# Power_Management.net
KiCad netlist of a schematic drawn in Altium Designer
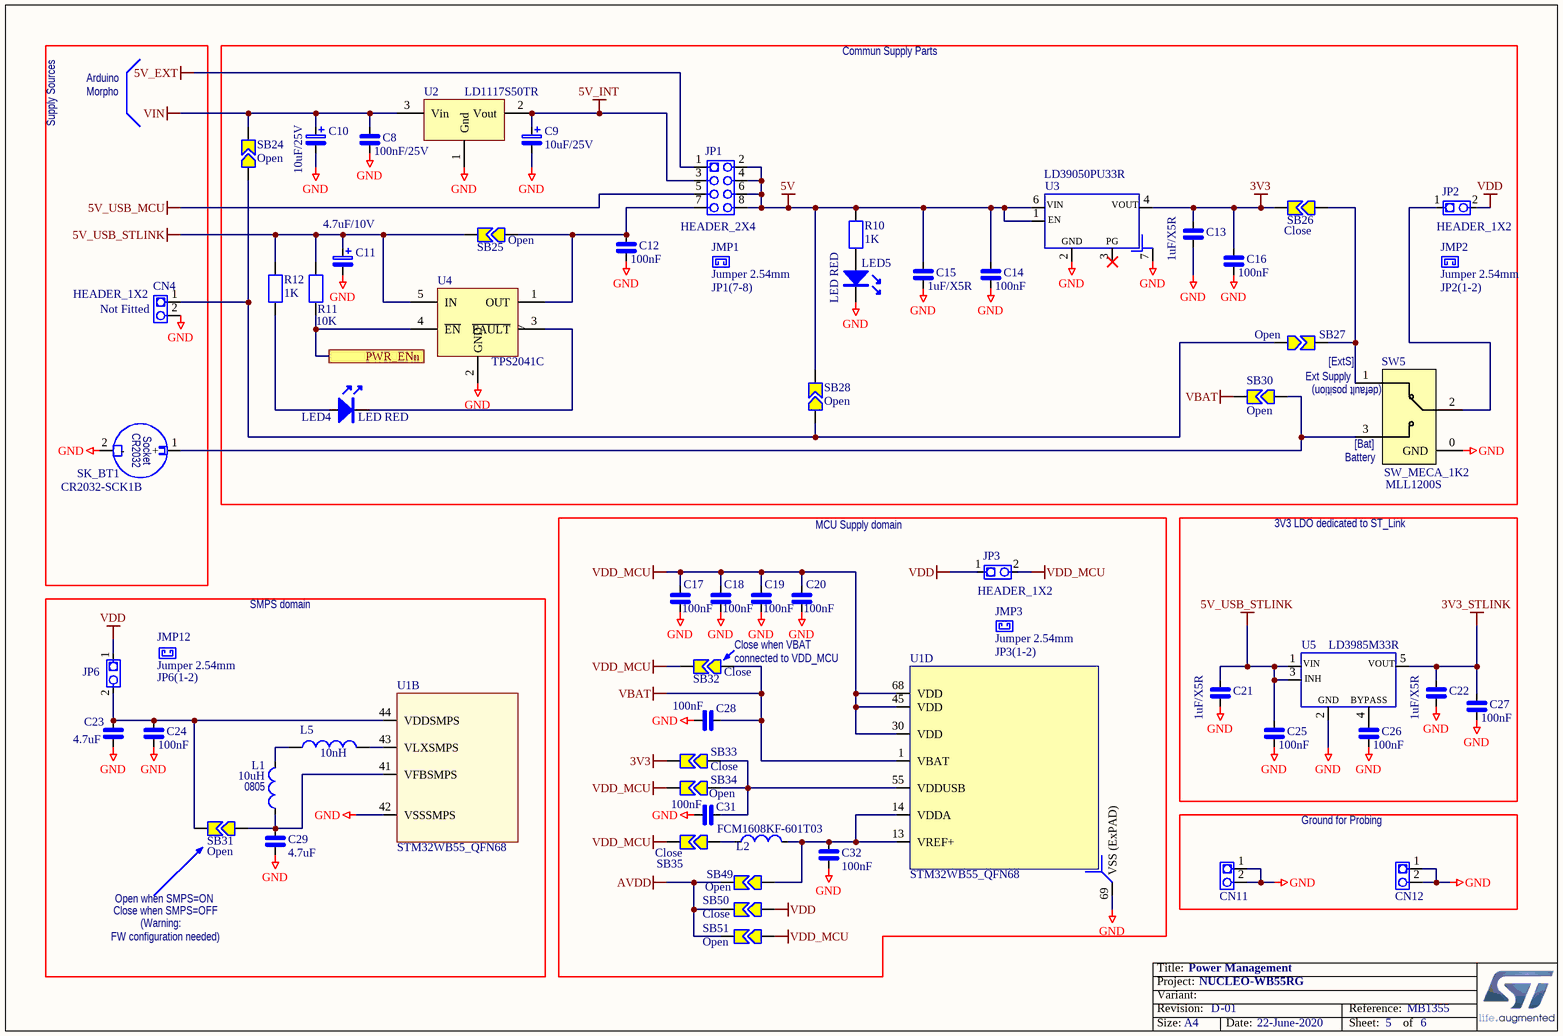
[diagram p0: Power_Management.SchDoc]

(export (version "E")
  (design (tool "Eeschema 10.0.6"))
  (components
    (comp (ref "C8")
      (value "100nF/25V")
      (footprint "0402_CAP_NPOL")
      (description "Capacitor_not polarized")
      (libsource (lib "ST_Lib3D") (part "CAP_NPOL"))
    )
    (comp (ref "C9")
      (value "10uF/25V")
      (footprint "1210_CAP_POL")
      (description "Condensateur_polarise")
      (libsource (lib "Passive") (part "CAP_POL"))
    )
    (comp (ref "C10")
      (value "10uF/25V")
      (footprint "1210_CAP_POL")
      (description "Condensateur_polarise")
      (libsource (lib "Passive") (part "CAP_POL"))
    )
    (comp (ref "C11")
      (value "4.7uF/10V")
      (footprint "1210_CAP_POL")
      (description "Condensateur_polarise")
      (libsource (lib "Passive") (part "CAP_POL"))
    )
    (comp (ref "C12")
      (value "100nF")
      (footprint "0402_CAP_NPOL")
      (description "Capacitor_not polarized")
      (libsource (lib "ST_Lib3D") (part "CAP_NPOL"))
    )
    (comp (ref "C13")
      (value "1uF/X5R")
      (footprint "0603_CAP_NPOL")
      (description "Capacitor_not polarized")
      (libsource (lib "ST_Lib3D") (part "CAP_NPOL"))
    )
    (comp (ref "C14")
      (value "100nF")
      (footprint "0402_CAP_NPOL")
      (description "Capacitor_not polarized")
      (libsource (lib "ST_Lib3D") (part "CAP_NPOL"))
    )
    (comp (ref "C15")
      (value "1uF/X5R")
      (footprint "0603_CAP_NPOL")
      (description "Capacitor_not polarized")
      (libsource (lib "ST_Lib3D") (part "CAP_NPOL"))
    )
    (comp (ref "C16")
      (value "100nF")
      (footprint "0402_CAP_NPOL")
      (description "Capacitor_not polarized")
      (libsource (lib "ST_Lib3D") (part "CAP_NPOL"))
    )
    (comp (ref "C17")
      (value "100nF")
      (footprint "0402_CAP_NPOL")
      (description "Capacitor_not polarized")
      (libsource (lib "ST_Lib3D") (part "CAP_NPOL"))
    )
    (comp (ref "C18")
      (value "100nF")
      (footprint "0402_CAP_NPOL")
      (description "Capacitor_not polarized")
      (libsource (lib "ST_Lib3D") (part "CAP_NPOL"))
    )
    (comp (ref "C19")
      (value "100nF")
      (footprint "0402_CAP_NPOL")
      (description "Capacitor_not polarized")
      (libsource (lib "ST_Lib3D") (part "CAP_NPOL"))
    )
    (comp (ref "C20")
      (value "100nF")
      (footprint "0402_CAP_NPOL")
      (description "Capacitor_not polarized")
      (libsource (lib "ST_Lib3D") (part "CAP_NPOL"))
    )
    (comp (ref "C21")
      (value "1uF/X5R")
      (footprint "0603_CAP_NPOL")
      (description "Capacitor_not polarized")
      (libsource (lib "ST_Lib3D") (part "CAP_NPOL"))
    )
    (comp (ref "C22")
      (value "1uF/X5R")
      (footprint "0603_CAP_NPOL")
      (description "Capacitor_not polarized")
      (libsource (lib "ST_Lib3D") (part "CAP_NPOL"))
    )
    (comp (ref "C23")
      (value "4.7uF")
      (footprint "0402_CAP_NPOL")
      (description "Capacitor_not polarized")
      (libsource (lib "ST_Lib3D") (part "CAP_NPOL"))
    )
    (comp (ref "C24")
      (value "100nF")
      (footprint "0402_CAP_NPOL")
      (description "Capacitor_not polarized")
      (libsource (lib "ST_Lib3D") (part "CAP_NPOL"))
    )
    (comp (ref "C25")
      (value "100nF")
      (footprint "0402_CAP_NPOL")
      (description "Capacitor_not polarized")
      (libsource (lib "ST_Lib3D") (part "CAP_NPOL"))
    )
    (comp (ref "C26")
      (value "100nF")
      (footprint "0402_CAP_NPOL")
      (description "Capacitor_not polarized")
      (libsource (lib "ST_Lib3D") (part "CAP_NPOL"))
    )
    (comp (ref "C27")
      (value "100nF")
      (footprint "0402_CAP_NPOL")
      (description "Capacitor_not polarized")
      (libsource (lib "ST_Lib3D") (part "CAP_NPOL"))
    )
    (comp (ref "C28")
      (value "100nF")
      (footprint "0402_CAP_NPOL")
      (description "Capacitor_not polarized")
      (libsource (lib "ST_Lib3D") (part "CAP_NPOL"))
    )
    (comp (ref "C29")
      (value "4.7uF")
      (footprint "0402_CAP_NPOL")
      (description "Capacitor_not polarized")
      (libsource (lib "ST_Lib3D") (part "CAP_NPOL"))
    )
    (comp (ref "C31")
      (value "100nF")
      (footprint "0402_CAP_NPOL")
      (description "Capacitor_not polarized")
      (libsource (lib "ST_Lib3D") (part "CAP_NPOL"))
    )
    (comp (ref "C32")
      (value "100nF")
      (footprint "0402_CAP_NPOL")
      (description "Capacitor_not polarized")
      (libsource (lib "ST_Lib3D") (part "CAP_NPOL"))
    )
    (comp (ref "CN4")
      (value "HEADER_1X2")
      (footprint "Header NF 1x2x2.54 TH")
      (fields (field (name "FITTED") "Not Fitted"))
      (libsource (lib "Connector") (part "HEADER_1X2"))
    )
    (comp (ref "CN11")
      (value "HEADER_1X2")
      (footprint "Header M 1x2x2.54 TH V")
      (libsource (lib "Connector") (part "HEADER_1X2"))
    )
    (comp (ref "CN12")
      (value "HEADER_1X2")
      (footprint "Header M 1x2x2.54 TH V")
      (libsource (lib "Connector") (part "HEADER_1X2"))
    )
    (comp (ref "JMP1")
      (value "Jumper 2.54mm")
      (footprint "Jumper 2.54mm BLACK")
      (fields (field (name "DEFAULT") "JP1(7-8)"))
      (libsource (lib "Connector") (part "Jumper 2.54mm"))
    )
    (comp (ref "JMP2")
      (value "Jumper 2.54mm")
      (footprint "Jumper 2.54mm BLACK")
      (fields (field (name "DEFAULT") "JP2(1-2)"))
      (libsource (lib "Connector") (part "Jumper 2.54mm"))
    )
    (comp (ref "JMP3")
      (value "Jumper 2.54mm")
      (footprint "Jumper 2.54mm BLACK")
      (fields (field (name "DEFAULT") "JP3(1-2)"))
      (libsource (lib "Connector") (part "Jumper 2.54mm"))
    )
    (comp (ref "JMP12")
      (value "Jumper 2.54mm")
      (footprint "Jumper 2.54mm BLACK")
      (fields (field (name "DEFAULT") "JP6(1-2)"))
      (libsource (lib "Connector") (part "Jumper 2.54mm"))
    )
    (comp (ref "JP1")
      (value "HEADER_2X4")
      (footprint "Header M 2x4x2.54 TH V")
      (libsource (lib "Connector") (part "HEADER_2X4"))
    )
    (comp (ref "JP2")
      (value "HEADER_1X2")
      (footprint "Header M 1x2x2.54 TH V")
      (libsource (lib "Connector") (part "HEADER_1X2_L"))
    )
    (comp (ref "JP3")
      (value "HEADER_1X2")
      (footprint "Header M 1x2x2.54 TH V")
      (libsource (lib "Connector") (part "HEADER_1X2_L"))
    )
    (comp (ref "JP6")
      (value "HEADER_1X2")
      (footprint "Header M 1x2x2.54 TH V")
      (libsource (lib "Connector") (part "HEADER_1X2_L"))
    )
    (comp (ref "L1")
      (value "10uH")
      (footprint "0805_COIL")
      (description "Coil Wurtz 10uH ref: 74479777310A")
      (libsource (lib "Passive") (part "IND_74479777310A"))
    )
    (comp (ref "L2")
      (value "FCM1608KF-601T03")
      (footprint "0603_COIL")
      (libsource (lib "Passive") (part "IND_FCM1608KF-601T03"))
    )
    (comp (ref "L5")
      (value "10nH")
      (footprint "IND_0402_MURATA_LQW15AN_H0P5")
      (description "inductor, 10nH +-2%, 100mA max,1.3 ohm DC max, Q min = 13,0402")
      (fields
        (field (name "INTERNAL_PART_NUMBER") "MCD-02063")
        (field (name "MANUFACTURER_PART_NUMBER") "LQP15MN10NG02")
        (field (name "PROVIDED_BY") "SUBCO")
      )
      (libsource (lib "MCD_PARTS_database") (part "Inductor"))
    )
    (comp (ref "LED4")
      (value "LED RED")
      (footprint "0603_LED_RED")
      (description "Light-Emitting Diode")
      (libsource (lib "Active") (part "LED"))
    )
    (comp (ref "LED5")
      (value "LED RED")
      (footprint "0603_LED_RED")
      (description "Light-Emitting Diode")
      (libsource (lib "Active") (part "LED"))
    )
    (comp (ref "R10")
      (value "1K")
      (footprint "0402_RES")
      (description "Resistor")
      (libsource (lib "Lib3D_Altium10_Schlib") (part "RES"))
    )
    (comp (ref "R11")
      (value "10K")
      (footprint "0402_RES")
      (description "Resistor")
      (libsource (lib "Lib3D_Altium10_Schlib") (part "RES"))
    )
    (comp (ref "R12")
      (value "1K")
      (footprint "0402_RES")
      (description "Resistor")
      (libsource (lib "Lib3D_Altium10_Schlib") (part "RES"))
    )
    (comp (ref "SB24")
      (value "Open")
      (footprint "SB-tiny")
      (description "Solder Jumper")
      (fields (field (name "PUBLISHER") "Altium Limited"))
      (libsource (lib "Passive") (part "Strap2"))
    )
    (comp (ref "SB25")
      (value "Open")
      (footprint "SB-tiny")
      (description "Solder Jumper")
      (fields (field (name "PUBLISHER") "Altium Limited"))
      (libsource (lib "Passive") (part "Strap2"))
    )
    (comp (ref "SB26")
      (value "Close")
      (footprint "SB-tiny")
      (description "Solder Jumper")
      (fields (field (name "PUBLISHER") "Altium Limited"))
      (libsource (lib "Passive") (part "Strap2"))
    )
    (comp (ref "SB27")
      (value "Open")
      (footprint "SB-tiny")
      (description "Solder Jumper")
      (fields (field (name "PUBLISHER") "Altium Limited"))
      (libsource (lib "Passive") (part "Strap2"))
    )
    (comp (ref "SB28")
      (value "Open")
      (footprint "SB-tiny")
      (description "Solder Jumper")
      (fields (field (name "PUBLISHER") "Altium Limited"))
      (libsource (lib "Passive") (part "Strap2"))
    )
    (comp (ref "SB30")
      (value "Open")
      (footprint "SB-tiny")
      (description "Solder Jumper")
      (fields (field (name "PUBLISHER") "Altium Limited"))
      (libsource (lib "Passive") (part "Strap2"))
    )
    (comp (ref "SB31")
      (value "Open")
      (footprint "SB-tiny")
      (description "Solder Jumper")
      (fields (field (name "PUBLISHER") "Altium Limited"))
      (libsource (lib "Passive") (part "Strap2"))
    )
    (comp (ref "SB32")
      (value "Close")
      (footprint "SB-tiny")
      (description "Solder Jumper")
      (fields (field (name "PUBLISHER") "Altium Limited"))
      (libsource (lib "Passive") (part "Strap2"))
    )
    (comp (ref "SB33")
      (value "Close")
      (footprint "SB-tiny")
      (description "Solder Jumper")
      (fields (field (name "PUBLISHER") "Altium Limited"))
      (libsource (lib "Passive") (part "Strap2"))
    )
    (comp (ref "SB34")
      (value "Open")
      (footprint "SB-tiny")
      (description "Solder Jumper")
      (fields (field (name "PUBLISHER") "Altium Limited"))
      (libsource (lib "Passive") (part "Strap2"))
    )
    (comp (ref "SB35")
      (value "Close")
      (footprint "SB-tiny")
      (description "Solder Jumper")
      (fields (field (name "PUBLISHER") "Altium Limited"))
      (libsource (lib "Passive") (part "Strap2"))
    )
    (comp (ref "SB49")
      (value "Open")
      (footprint "SB-tiny")
      (description "Solder Jumper")
      (fields (field (name "PUBLISHER") "Altium Limited"))
      (libsource (lib "Passive") (part "Strap2"))
    )
    (comp (ref "SB50")
      (value "Close")
      (footprint "SB-tiny")
      (description "Solder Jumper")
      (fields (field (name "PUBLISHER") "Altium Limited"))
      (libsource (lib "Passive") (part "Strap2"))
    )
    (comp (ref "SB51")
      (value "Open")
      (footprint "SB-tiny")
      (description "Solder Jumper")
      (fields (field (name "PUBLISHER") "Altium Limited"))
      (libsource (lib "Passive") (part "Strap2"))
    )
    (comp (ref "SK_BT1")
      (value "CR2032-SCK1B")
      (footprint "CR2032-SCK1")
      (libsource (lib "Battery_Acc_Generator") (part "CR2032-SCK1B"))
    )
    (comp (ref "SW5")
      (value "SW_MECA_1K2")
      (footprint "SWI_SPDT-RA_TE-CONNECTIVITY_MLL1200S_1P2T")
      (description "SPDT RA SMT SLIDE SWITCH")
      (fields
        (field (name "INTERNAL_PART_NUMBER") "MCD-02081")
        (field (name "ALTIUM_VALUE") "MLL1200S")
        (field (name "MANUFACTURER_PART_NUMBER") "MLL1200S")
        (field (name "PROVIDED_BY") "SUBCO")
      )
      (libsource (lib "MCD_PARTS_database") (part "SW_MECA_1K2"))
    )
    (comp (ref "U1")
      (value "STM32WB55_QFN68")
      (footprint "VFQFPN68_8x8x0.1_p0.4")
      (libsource (lib "Active") (part "STM32WBxx_QFN68"))
    )
    (comp (ref "U2")
      (value "LD1117S50TR")
      (footprint "SOT223_SC73_A")
      (description "IC REG LDO 5V 0.8A SOT223")
      (libsource (lib "Active") (part "LD1117S50TR"))
    )
    (comp (ref "U3")
      (value "LD39050PU33R")
      (footprint "DFN6 3x3mm")
      (description "3.3V voltage regulator 500mA")
      (libsource (lib "Active") (part "LD39050PU33R"))
    )
    (comp (ref "U4")
      (value "TPS2041C")
      (footprint "MOS_SOT23-5L")
      (description "5V Power Switch, 0.85A, RDSon 130mOhm max, with active low enable pin")
      (fields
        (field (name "INTERNAL_PART_NUMBER") "MCD-01785")
        (field (name "MANUFACTURER_PART_NUMBER") "TPS2041CDBVT")
        (field (name "PROVIDED_BY") "SUBCO")
      )
      (libsource (lib "MCD_PARTS_database") (part "TPS2041C"))
    )
    (comp (ref "U5")
      (value "LD3985M33R")
      (footprint "SOT23-5")
      (description "3.3V low drop voltage regulator")
      (fields (field (name "MANUFACTURER") "STMicroelectronics"))
      (libsource (lib "Active") (part "LD3985M33R"))
    )
  )
  (nets
    (net (code "1") (name "/PWR_ENn") (class "Default")
      (node (ref "R11") (pin "2") (pinfunction "2_2") (pintype "passive"))
      (node (ref "U4") (pin "4") (pinfunction "~{EN}_4") (pintype "passive"))
    )
    (net (code "2") (name "3V3") (class "Default")
      (node (ref "C13") (pin "1") (pinfunction "1_1") (pintype "passive"))
      (node (ref "C16") (pin "1") (pinfunction "1_1") (pintype "passive"))
      (node (ref "SB26") (pin "2") (pinfunction "2_2") (pintype "passive"))
      (node (ref "SB33") (pin "2") (pinfunction "2_2") (pintype "passive"))
      (node (ref "U3") (pin "4") (pinfunction "VOUT_4") (pintype "passive"))
    )
    (net (code "3") (name "3V3_STLINK") (class "Default")
      (node (ref "C22") (pin "1") (pinfunction "1_1") (pintype "passive"))
      (node (ref "C27") (pin "1") (pinfunction "1_1") (pintype "passive"))
      (node (ref "U5") (pin "5") (pinfunction "VOUT_5") (pintype "passive"))
    )
    (net (code "4") (name "5V") (class "Default")
      (node (ref "C14") (pin "1") (pinfunction "1_1") (pintype "passive"))
      (node (ref "C15") (pin "1") (pinfunction "1_1") (pintype "passive"))
      (node (ref "JP1") (pin "2") (pintype "passive"))
      (node (ref "JP1") (pin "4") (pintype "passive"))
      (node (ref "JP1") (pin "6") (pintype "passive"))
      (node (ref "JP1") (pin "8") (pintype "passive"))
      (node (ref "R10") (pin "1") (pinfunction "1_1") (pintype "passive"))
      (node (ref "SB28") (pin "2") (pinfunction "2_2") (pintype "passive"))
      (node (ref "U3") (pin "1") (pinfunction "EN_1") (pintype "passive"))
      (node (ref "U3") (pin "6") (pinfunction "VIN_6") (pintype "passive"))
    )
    (net (code "5") (name "5V_EXT") (class "Default") (node (ref "JP1") (pin "1") (pintype "passive")))
    (net (code "6") (name "5V_INT") (class "Default")
      (node (ref "C9") (pin "1") (pintype "passive"))
      (node (ref "JP1") (pin "3") (pintype "passive"))
      (node (ref "U2") (pin "2") (pinfunction "Vout_2") (pintype "passive"))
    )
    (net (code "7") (name "5V_USB_MCU") (class "Default") (node (ref "JP1") (pin "5") (pintype "passive")))
    (net (code "8") (name "5V_USB_STLINK") (class "Default")
      (node (ref "C11") (pin "1") (pintype "passive"))
      (node (ref "C21") (pin "1") (pinfunction "1_1") (pintype "passive"))
      (node (ref "C25") (pin "1") (pinfunction "1_1") (pintype "passive"))
      (node (ref "R11") (pin "1") (pinfunction "1_1") (pintype "passive"))
      (node (ref "R12") (pin "1") (pinfunction "1_1") (pintype "passive"))
      (node (ref "SB25") (pin "2") (pinfunction "2_2") (pintype "passive"))
      (node (ref "U4") (pin "5") (pinfunction "IN_5") (pintype "passive"))
      (node (ref "U5") (pin "1") (pinfunction "VIN_1") (pintype "passive"))
      (node (ref "U5") (pin "3") (pinfunction "CE_3") (pintype "passive"))
    )
    (net (code "9") (name "AVDD") (class "Default")
      (node (ref "SB49") (pin "2") (pinfunction "2_2") (pintype "passive"))
      (node (ref "SB50") (pin "2") (pinfunction "2_2") (pintype "passive"))
      (node (ref "SB51") (pin "2") (pinfunction "2_2") (pintype "passive"))
    )
    (net (code "10") (name "GND") (class "Default")
      (node (ref "C10") (pin "2") (pintype "passive"))
      (node (ref "C11") (pin "2") (pintype "passive"))
      (node (ref "C12") (pin "2") (pinfunction "2_2") (pintype "passive"))
      (node (ref "C13") (pin "2") (pinfunction "2_2") (pintype "passive"))
      (node (ref "C14") (pin "2") (pinfunction "2_2") (pintype "passive"))
      (node (ref "C15") (pin "2") (pinfunction "2_2") (pintype "passive"))
      (node (ref "C16") (pin "2") (pinfunction "2_2") (pintype "passive"))
      (node (ref "C17") (pin "2") (pinfunction "2_2") (pintype "passive"))
      (node (ref "C18") (pin "2") (pinfunction "2_2") (pintype "passive"))
      (node (ref "C19") (pin "2") (pinfunction "2_2") (pintype "passive"))
      (node (ref "C20") (pin "2") (pinfunction "2_2") (pintype "passive"))
      (node (ref "C21") (pin "2") (pinfunction "2_2") (pintype "passive"))
      (node (ref "C22") (pin "2") (pinfunction "2_2") (pintype "passive"))
      (node (ref "C23") (pin "2") (pinfunction "2_2") (pintype "passive"))
      (node (ref "C24") (pin "2") (pinfunction "2_2") (pintype "passive"))
      (node (ref "C25") (pin "2") (pinfunction "2_2") (pintype "passive"))
      (node (ref "C26") (pin "2") (pinfunction "2_2") (pintype "passive"))
      (node (ref "C27") (pin "2") (pinfunction "2_2") (pintype "passive"))
      (node (ref "C28") (pin "2") (pinfunction "2_2") (pintype "passive"))
      (node (ref "C29") (pin "2") (pinfunction "2_2") (pintype "passive"))
      (node (ref "C31") (pin "2") (pinfunction "2_2") (pintype "passive"))
      (node (ref "C32") (pin "2") (pinfunction "2_2") (pintype "passive"))
      (node (ref "C8") (pin "2") (pinfunction "2_2") (pintype "passive"))
      (node (ref "C9") (pin "2") (pintype "passive"))
      (node (ref "CN11") (pin "1") (pinfunction "1_1") (pintype "passive"))
      (node (ref "CN11") (pin "2") (pinfunction "2_2") (pintype "passive"))
      (node (ref "CN12") (pin "1") (pinfunction "1_1") (pintype "passive"))
      (node (ref "CN12") (pin "2") (pinfunction "2_2") (pintype "passive"))
      (node (ref "CN4") (pin "2") (pinfunction "2_2") (pintype "passive"))
      (node (ref "LED5") (pin "K") (pinfunction "K_K") (pintype "passive"))
      (node (ref "SK_BT1") (pin "2") (pinfunction "-_2") (pintype "passive"))
      (node (ref "SW5") (pin "0") (pinfunction "GND_0") (pintype "passive"))
      (node (ref "U1") (pin "42") (pinfunction "VSSSMPS_42") (pintype "passive"))
      (node (ref "U1") (pin "69") (pinfunction "VSS_(ExPAD)_69") (pintype "passive"))
      (node (ref "U2") (pin "1") (pinfunction "Gnd_1") (pintype "passive"))
      (node (ref "U3") (pin "2") (pinfunction "VSS_2") (pintype "passive"))
      (node (ref "U3") (pin "7") (pinfunction "7_7") (pintype "passive"))
      (node (ref "U4") (pin "2") (pinfunction "GND_2") (pintype "passive"))
      (node (ref "U5") (pin "2") (pinfunction "VSS_2") (pintype "passive"))
    )
    (net (code "11") (name "Net-(CN4-Pad1)") (class "Default")
      (node (ref "CN4") (pin "1") (pinfunction "1_1") (pintype "passive"))
      (node (ref "SB24") (pin "1") (pinfunction "1_1") (pintype "passive"))
      (node (ref "SB27") (pin "1") (pinfunction "1_1") (pintype "passive"))
      (node (ref "SB28") (pin "1") (pinfunction "1_1") (pintype "passive"))
    )
    (net (code "12") (name "Net-(JP2-Pad1)") (class "Default")
      (node (ref "JP2") (pin "1") (pinfunction "1_1") (pintype "passive"))
      (node (ref "SW5") (pin "2") (pinfunction "2_2") (pintype "passive"))
    )
    (net (code "13") (name "Net-(L1-Pad2)") (class "Default")
      (node (ref "L1") (pin "2") (pinfunction "2_2") (pintype "passive"))
      (node (ref "L5") (pin "1") (pinfunction "1_1") (pintype "passive"))
    )
    (net (code "14") (name "Net-(L2-Pad1)") (class "Default")
      (node (ref "L2") (pin "1") (pinfunction "1_1") (pintype "passive"))
      (node (ref "SB35") (pin "1") (pinfunction "1_1") (pintype "passive"))
    )
    (net (code "15") (name "Net-(LED4-PadA)") (class "Default")
      (node (ref "LED4") (pin "A") (pinfunction "A_A") (pintype "passive"))
      (node (ref "R12") (pin "2") (pinfunction "2_2") (pintype "passive"))
    )
    (net (code "16") (name "Net-(LED5-PadA)") (class "Default")
      (node (ref "LED5") (pin "A") (pinfunction "A_A") (pintype "passive"))
      (node (ref "R10") (pin "2") (pinfunction "2_2") (pintype "passive"))
    )
    (net (code "17") (name "Net-(SB26-Pad1)") (class "Default")
      (node (ref "SB26") (pin "1") (pinfunction "1_1") (pintype "passive"))
      (node (ref "SB27") (pin "2") (pinfunction "2_2") (pintype "passive"))
      (node (ref "SW5") (pin "1") (pinfunction "1_1") (pintype "passive"))
    )
    (net (code "18") (name "Net-(SK_BT1-+)") (class "Default")
      (node (ref "SB30") (pin "1") (pinfunction "1_1") (pintype "passive"))
      (node (ref "SK_BT1") (pin "1") (pinfunction "+_1") (pintype "passive"))
      (node (ref "SW5") (pin "3") (pinfunction "3_3") (pintype "passive"))
    )
    (net (code "19") (name "Net-(U1B-VDDSMPS)") (class "Default")
      (node (ref "C23") (pin "1") (pinfunction "1_1") (pintype "passive"))
      (node (ref "C24") (pin "1") (pinfunction "1_1") (pintype "passive"))
      (node (ref "JP6") (pin "2") (pinfunction "2_2") (pintype "passive"))
      (node (ref "SB31") (pin "2") (pinfunction "2_2") (pintype "passive"))
      (node (ref "U1") (pin "44") (pinfunction "VDDSMPS_44") (pintype "passive"))
    )
    (net (code "20") (name "Net-(U1B-VFBSMPS)") (class "Default")
      (node (ref "C29") (pin "1") (pinfunction "1_1") (pintype "passive"))
      (node (ref "L1") (pin "1") (pinfunction "1_1") (pintype "passive"))
      (node (ref "SB31") (pin "1") (pinfunction "1_1") (pintype "passive"))
      (node (ref "U1") (pin "41") (pinfunction "VFBSMPS_41") (pintype "passive"))
    )
    (net (code "21") (name "Net-(U1B-VLXSMPS)") (class "Default")
      (node (ref "L5") (pin "2") (pinfunction "2_2") (pintype "passive"))
      (node (ref "U1") (pin "43") (pinfunction "VLXSMPS_43") (pintype "passive"))
    )
    (net (code "22") (name "Net-(U1D-VDDA)") (class "Default")
      (node (ref "C32") (pin "1") (pinfunction "1_1") (pintype "passive"))
      (node (ref "L2") (pin "2") (pinfunction "2_2") (pintype "passive"))
      (node (ref "SB49") (pin "1") (pinfunction "1_1") (pintype "passive"))
      (node (ref "U1") (pin "13") (pinfunction "VREF+_13") (pintype "passive"))
      (node (ref "U1") (pin "14") (pinfunction "VDDA_14") (pintype "passive"))
    )
    (net (code "23") (name "Net-(U1D-VDDUSB)") (class "Default")
      (node (ref "C31") (pin "1") (pinfunction "1_1") (pintype "passive"))
      (node (ref "SB33") (pin "1") (pinfunction "1_1") (pintype "passive"))
      (node (ref "SB34") (pin "1") (pinfunction "1_1") (pintype "passive"))
      (node (ref "U1") (pin "55") (pinfunction "VDDUSB_55") (pintype "passive"))
    )
    (net (code "24") (name "Net-(U4-OUT)") (class "Default")
      (node (ref "C12") (pin "1") (pinfunction "1_1") (pintype "passive"))
      (node (ref "JP1") (pin "7") (pintype "passive"))
      (node (ref "SB25") (pin "1") (pinfunction "1_1") (pintype "passive"))
      (node (ref "U4") (pin "1") (pinfunction "OUT_1") (pintype "passive"))
    )
    (net (code "25") (name "Net-(U4-~{FAULT})") (class "Default")
      (node (ref "LED4") (pin "K") (pinfunction "K_K") (pintype "passive"))
      (node (ref "U4") (pin "3") (pinfunction "~{FAULT}_3") (pintype "passive"))
    )
    (net (code "26") (name "Net-(U5-BYPASS)") (class "Default")
      (node (ref "C26") (pin "1") (pinfunction "1_1") (pintype "passive"))
      (node (ref "U5") (pin "4") (pinfunction "BYPASS_4") (pintype "passive"))
    )
    (net (code "27") (name "VBAT") (class "Default")
      (node (ref "C28") (pin "1") (pinfunction "1_1") (pintype "passive"))
      (node (ref "SB30") (pin "2") (pinfunction "2_2") (pintype "passive"))
      (node (ref "SB32") (pin "1") (pinfunction "1_1") (pintype "passive"))
      (node (ref "U1") (pin "1") (pinfunction "VBAT_1") (pintype "passive"))
    )
    (net (code "28") (name "VDD") (class "Default")
      (node (ref "JP2") (pin "2") (pinfunction "2_2") (pintype "passive"))
      (node (ref "JP3") (pin "1") (pinfunction "1_1") (pintype "passive"))
      (node (ref "JP6") (pin "1") (pinfunction "1_1") (pintype "passive"))
      (node (ref "SB50") (pin "1") (pinfunction "1_1") (pintype "passive"))
    )
    (net (code "29") (name "VDD_MCU") (class "Default")
      (node (ref "C17") (pin "1") (pinfunction "1_1") (pintype "passive"))
      (node (ref "C18") (pin "1") (pinfunction "1_1") (pintype "passive"))
      (node (ref "C19") (pin "1") (pinfunction "1_1") (pintype "passive"))
      (node (ref "C20") (pin "1") (pinfunction "1_1") (pintype "passive"))
      (node (ref "JP3") (pin "2") (pinfunction "2_2") (pintype "passive"))
      (node (ref "SB32") (pin "2") (pinfunction "2_2") (pintype "passive"))
      (node (ref "SB34") (pin "2") (pinfunction "2_2") (pintype "passive"))
      (node (ref "SB35") (pin "2") (pinfunction "2_2") (pintype "passive"))
      (node (ref "SB51") (pin "1") (pinfunction "1_1") (pintype "passive"))
      (node (ref "U1") (pin "30") (pinfunction "VDD_30") (pintype "passive"))
      (node (ref "U1") (pin "45") (pinfunction "VDD_45") (pintype "passive"))
      (node (ref "U1") (pin "68") (pinfunction "VDD_68") (pintype "passive"))
    )
    (net (code "30") (name "VIN") (class "Default")
      (node (ref "C10") (pin "1") (pintype "passive"))
      (node (ref "C8") (pin "1") (pinfunction "1_1") (pintype "passive"))
      (node (ref "SB24") (pin "2") (pinfunction "2_2") (pintype "passive"))
      (node (ref "U2") (pin "3") (pinfunction "Vin_3") (pintype "passive"))
    )
    (net (code "31") (name "unconnected-(U3-PG-Pad3)") (class "Default")
      (node (ref "U3") (pin "3") (pinfunction "PG_3") (pintype "passive+no_connect"))
    )
  )
)
